# OLM_OS_v142.net
KiCad netlist of a schematic drawn in EAGLE
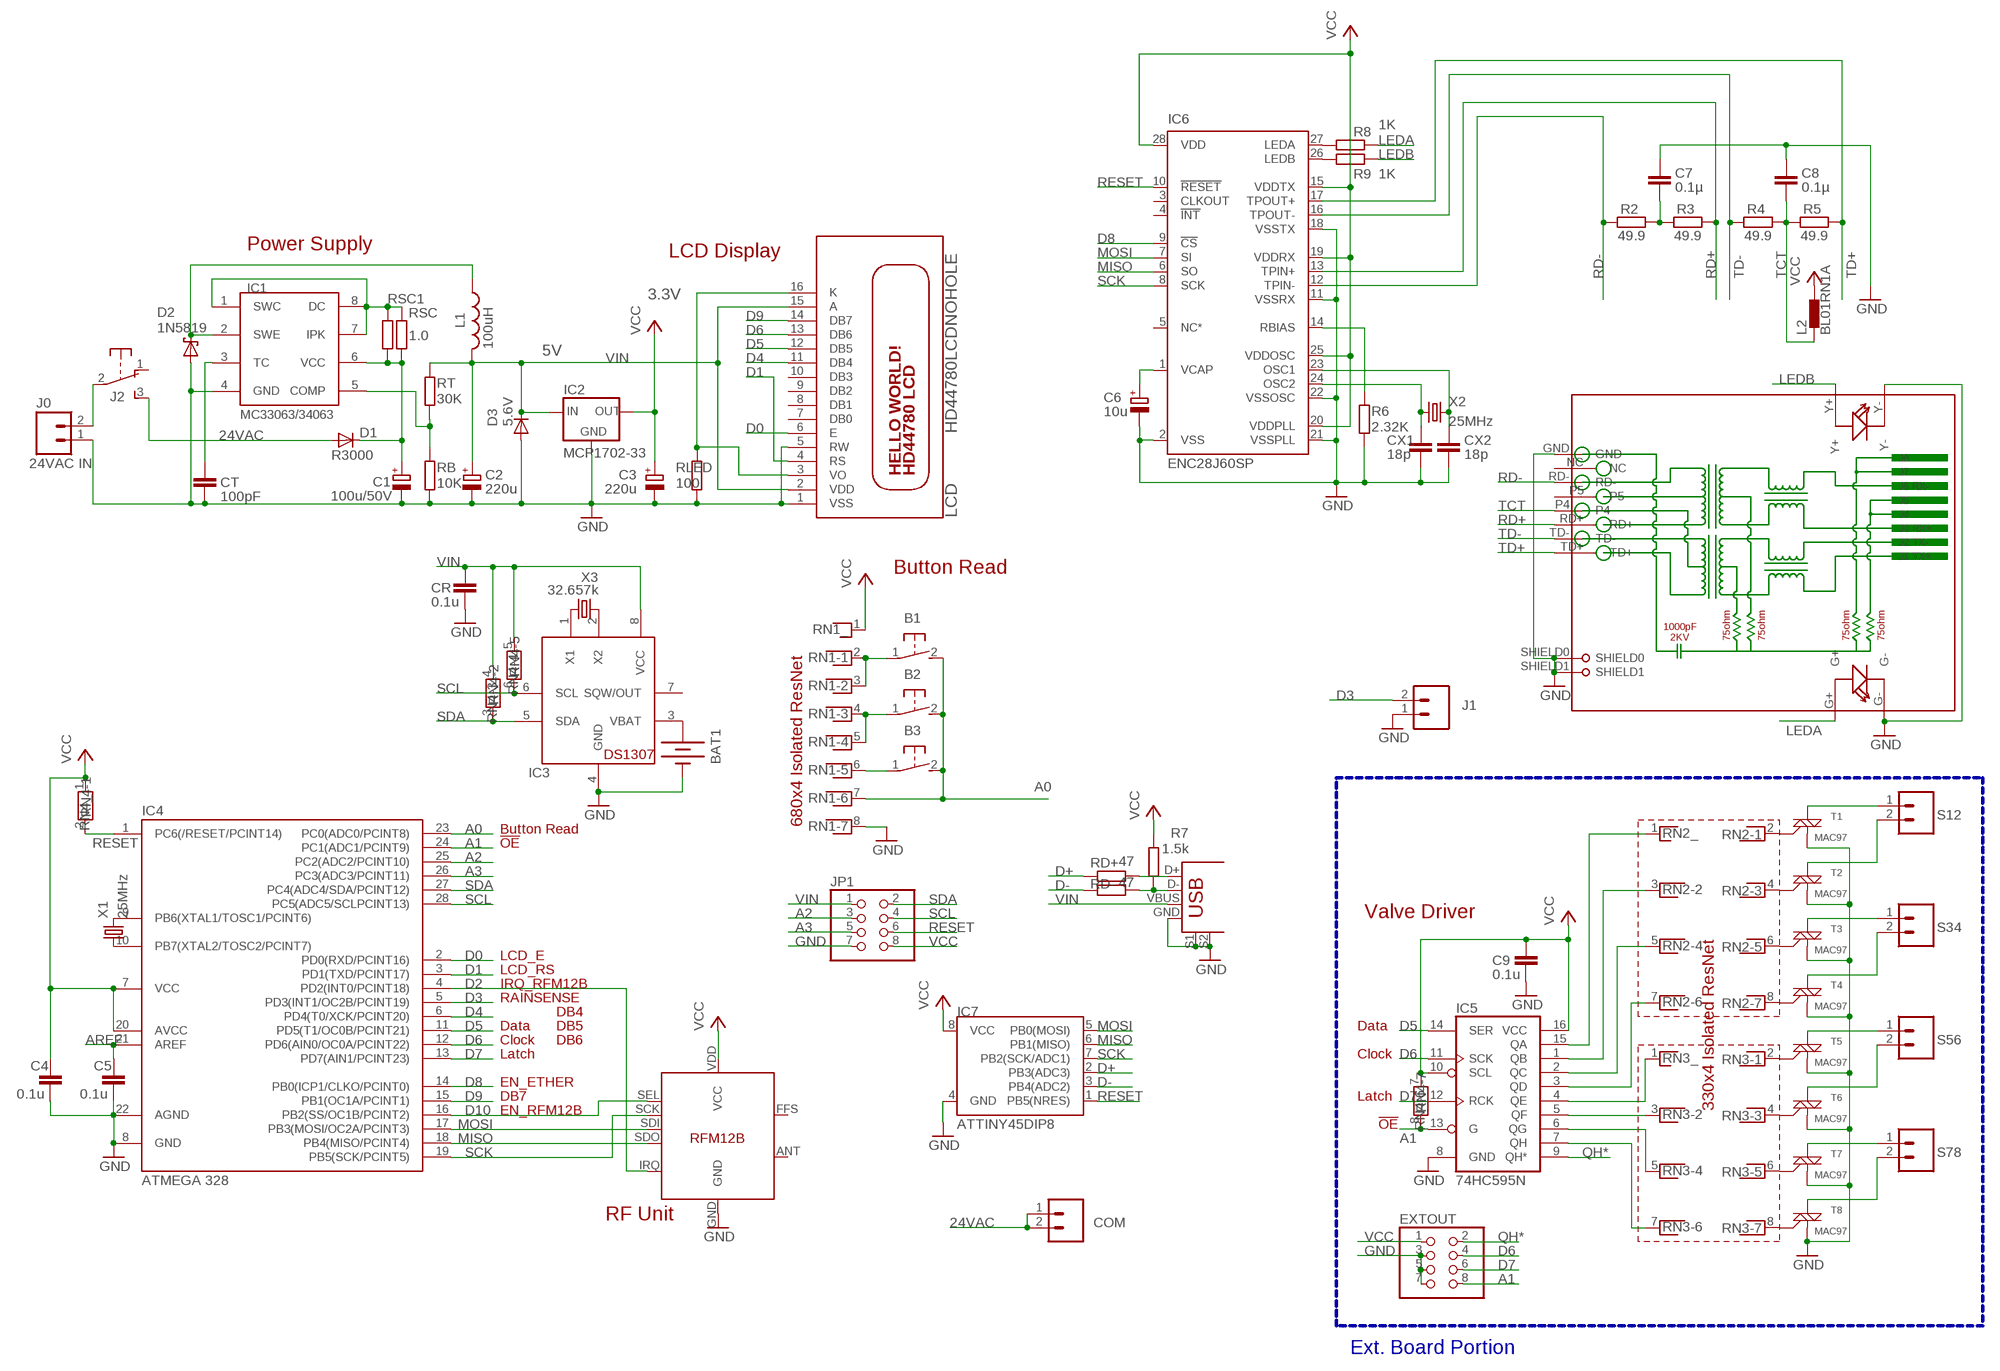
[diagram p0: schematic, sheet 1]

(export (version "E")
  (design (tool "Eeschema 10.0.6"))
  (components
    (comp (ref "B1")
      (value "31-XX")
      (footprint "eagle-import:B3F-31XX")
      (libsource (lib "eagle-import") (part "31-XX"))
    )
    (comp (ref "B2")
      (value "31-XX")
      (footprint "eagle-import:B3F-31XX")
      (libsource (lib "eagle-import") (part "31-XX"))
    )
    (comp (ref "B3")
      (value "31-XX")
      (footprint "eagle-import:B3F-31XX")
      (libsource (lib "eagle-import") (part "31-XX"))
    )
    (comp (ref "BAT1")
      (value "BATTERY12PTH")
      (footprint "eagle-import:BATTCON_12MM_PTH")
      (libsource (lib "eagle-import") (part "BATTERY12PTH"))
    )
    (comp (ref "C1")
      (value "100u/50V")
      (footprint "eagle-import:E3,5-8")
      (libsource (lib "eagle-import") (part "CPOL-EUE3.5-8"))
    )
    (comp (ref "C2")
      (value "220u")
      (footprint "eagle-import:E2-5")
      (libsource (lib "eagle-import") (part "CPOL-EUE2-5"))
    )
    (comp (ref "C3")
      (value "220u")
      (footprint "eagle-import:E2-5")
      (libsource (lib "eagle-import") (part "CPOL-EUE2-5"))
    )
    (comp (ref "C4")
      (value "0.1u")
      (footprint "eagle-import:C025-024X044")
      (libsource (lib "eagle-import") (part "C-EU025-024X044"))
    )
    (comp (ref "C5")
      (value "0.1u")
      (footprint "eagle-import:C025-024X044")
      (libsource (lib "eagle-import") (part "C-EU025-024X044"))
    )
    (comp (ref "C6")
      (value "10u")
      (footprint "eagle-import:E1,8-4")
      (libsource (lib "eagle-import") (part "CPOL-EUE1.8-4"))
    )
    (comp (ref "C7")
      (value "0.1µ")
      (footprint "eagle-import:C025-024X044")
      (libsource (lib "eagle-import") (part "resistor_C-EU025-024X044"))
    )
    (comp (ref "C8")
      (value "0.1µ")
      (footprint "eagle-import:C025-024X044")
      (libsource (lib "eagle-import") (part "resistor_C-EU025-024X044"))
    )
    (comp (ref "C9")
      (value "0.1u")
      (footprint "eagle-import:C025-024X044")
      (libsource (lib "eagle-import") (part "C-EU025-024X044"))
    )
    (comp (ref "COM")
      (value "M025MM")
      (footprint "eagle-import:SCREWTERMINAL-5MM-2")
      (libsource (lib "eagle-import") (part "M025MM"))
    )
    (comp (ref "CR")
      (value "0.1u")
      (footprint "eagle-import:C025-024X044")
      (libsource (lib "eagle-import") (part "C-EU025-024X044"))
    )
    (comp (ref "CT")
      (value "100pF")
      (footprint "eagle-import:C025-024X044")
      (libsource (lib "eagle-import") (part "C-EU025-024X044"))
    )
    (comp (ref "CX1")
      (value "18p")
      (footprint "eagle-import:C025-024X044")
      (libsource (lib "eagle-import") (part "resistor_C-EU025-024X044"))
    )
    (comp (ref "CX2")
      (value "18p")
      (footprint "eagle-import:C025-024X044")
      (libsource (lib "eagle-import") (part "resistor_C-EU025-024X044"))
    )
    (comp (ref "D1")
      (value "R3000")
      (footprint "eagle-import:DO41-7.6")
      (libsource (lib "eagle-import") (part "DIODE-DO41-7.6"))
    )
    (comp (ref "D2")
      (value "1N5819")
      (footprint "eagle-import:DO41-7.6")
      (libsource (lib "eagle-import") (part "1N5817-B"))
    )
    (comp (ref "D3")
      (value "5.6V")
      (footprint "eagle-import:DO35-7")
      (libsource (lib "eagle-import") (part "1N4148DO35-7"))
    )
    (comp (ref "EXTOUT")
      (value "PINHD-2X4")
      (footprint "eagle-import:2X04")
      (libsource (lib "eagle-import") (part "PINHD-2X4"))
    )
    (comp (ref "IC1")
      (value "MC33063/MC34063P")
      (footprint "eagle-import:DIL08")
      (libsource (lib "eagle-import") (part "MC33063/MC34063P"))
    )
    (comp (ref "IC2")
      (value "MCP1702-33")
      (footprint "eagle-import:TO92-INLINE")
      (libsource (lib "eagle-import") (part "MCP1700INLINE"))
    )
    (comp (ref "IC3")
      (value "DS1307")
      (footprint "eagle-import:DIL08")
      (libsource (lib "eagle-import") (part "DS1307"))
    )
    (comp (ref "IC4")
      (value "ATMEGA 328")
      (footprint "eagle-import:DIL28-3")
      (libsource (lib "eagle-import") (part "ATMEGA48/88/168-PU"))
    )
    (comp (ref "IC5")
      (value "74HC595N")
      (footprint "eagle-import:DIL16")
      (libsource (lib "eagle-import") (part "74595NLS"))
    )
    (comp (ref "IC6")
      (value "ENC28J60SP")
      (footprint "eagle-import:DIL28-3")
      (fields (field (name "MF") "MICROCHIP") (field (name "MPN") "ENC28J60/SP"))
      (libsource (lib "eagle-import") (part "ENC28J60SP"))
    )
    (comp (ref "IC7")
      (value "ATTINY45DIP8")
      (footprint "eagle-import:DIP08")
      (libsource (lib "eagle-import") (part "ATTINY45DIP8"))
    )
    (comp (ref "IC8")
      (value "RFM12B")
      (footprint "eagle-import:RFM12B")
      (libsource (lib "eagle-import") (part "RFM12B"))
    )
    (comp (ref "J0")
      (value "24VAC IN")
      (footprint "eagle-import:SCREWTERMINAL-5MM-2")
      (libsource (lib "eagle-import") (part "M025MM"))
    )
    (comp (ref "J1")
      (value "M025MM")
      (footprint "eagle-import:SCREWTERMINAL-5MM-2")
      (libsource (lib "eagle-import") (part "M025MM"))
    )
    (comp (ref "J2")
      (value "EG1206")
      (footprint "eagle-import:EG1206")
      (libsource (lib "eagle-import") (part "EG1206"))
    )
    (comp (ref "JP1")
      (value "PINHD-2X4")
      (footprint "eagle-import:2X04")
      (libsource (lib "eagle-import") (part "PINHD-2X4"))
    )
    (comp (ref "L1")
      (value "100uH")
      (footprint "eagle-import:6000-XXXX-RC")
      (libsource (lib "eagle-import") (part "L-US6000-XXX-RC"))
    )
    (comp (ref "L2")
      (value "BL01RN1A")
      (footprint "eagle-import:BL01RN1A")
      (libsource (lib "eagle-import") (part "BL01RN1A"))
    )
    (comp (ref "LCD")
      (value "HD44780LCDNOHOLE")
      (footprint "eagle-import:LCD1602A")
      (libsource (lib "eagle-import") (part "HD44780LCDNOHOLE"))
    )
    (comp (ref "R2")
      (value "49.9")
      (footprint "eagle-import:0204_7")
      (libsource (lib "eagle-import") (part "R-EU_0204/7"))
    )
    (comp (ref "R3")
      (value "49.9")
      (footprint "eagle-import:0204_7")
      (libsource (lib "eagle-import") (part "R-EU_0204/7"))
    )
    (comp (ref "R4")
      (value "49.9")
      (footprint "eagle-import:0204_7")
      (libsource (lib "eagle-import") (part "R-EU_0204/7"))
    )
    (comp (ref "R5")
      (value "49.9")
      (footprint "eagle-import:0204_7")
      (libsource (lib "eagle-import") (part "R-EU_0204/7"))
    )
    (comp (ref "R6")
      (value "2.32K")
      (footprint "eagle-import:0204_7")
      (libsource (lib "eagle-import") (part "R-EU_0204/7"))
    )
    (comp (ref "R7")
      (value "1.5k")
      (footprint "eagle-import:0204_7")
      (libsource (lib "eagle-import") (part "R-EU_0204/7"))
    )
    (comp (ref "R8")
      (value "1K")
      (footprint "eagle-import:0204_7")
      (libsource (lib "eagle-import") (part "R-EU_0204/7"))
    )
    (comp (ref "R9")
      (value "1K")
      (footprint "eagle-import:0204_7")
      (libsource (lib "eagle-import") (part "R-EU_0204/7"))
    )
    (comp (ref "RB")
      (value "10K")
      (footprint "eagle-import:0204_7")
      (libsource (lib "eagle-import") (part "R-EU_0204/7"))
    )
    (comp (ref "RD+")
      (value "47")
      (footprint "eagle-import:0204_7")
      (libsource (lib "eagle-import") (part "R-EU_0204/7"))
    )
    (comp (ref "RD-")
      (value "47")
      (footprint "eagle-import:0204_7")
      (libsource (lib "eagle-import") (part "R-EU_0204/7"))
    )
    (comp (ref "RJ1")
      (value "HR911105A")
      (footprint "eagle-import:HR911105A")
      (libsource (lib "eagle-import") (part "HR911105A"))
    )
    (comp (ref "RLED")
      (value "100")
      (footprint "eagle-import:0204_7")
      (libsource (lib "eagle-import") (part "R-EU_0204/7"))
    )
    (comp (ref "RN1")
      (value "RNX7")
      (footprint "eagle-import:RN-8")
      (libsource (lib "eagle-import") (part "RNX7"))
    )
    (comp (ref "RN2")
      (value "RNX7")
      (footprint "eagle-import:RN-8")
      (libsource (lib "eagle-import") (part "RNX7"))
    )
    (comp (ref "RN3")
      (value "RNX7")
      (footprint "eagle-import:RN-8")
      (libsource (lib "eagle-import") (part "RNX7"))
    )
    (comp (ref "RN4")
      (value "RNX7")
      (footprint "eagle-import:RN-8")
      (libsource (lib "eagle-import") (part "RNX7"))
    )
    (comp (ref "RSC")
      (value "1.0")
      (footprint "eagle-import:0204_7")
      (libsource (lib "eagle-import") (part "R-EU_0204/7"))
    )
    (comp (ref "RSC1")
      (value "1.0")
      (footprint "eagle-import:0204_7")
      (libsource (lib "eagle-import") (part "R-EU_0204/7"))
    )
    (comp (ref "RT")
      (value "30K")
      (footprint "eagle-import:0204_7")
      (libsource (lib "eagle-import") (part "R-EU_0204/7"))
    )
    (comp (ref "S12")
      (value "M025MM")
      (footprint "eagle-import:SCREWTERMINAL-5MM-2")
      (libsource (lib "eagle-import") (part "M025MM"))
    )
    (comp (ref "S34")
      (value "M025MM")
      (footprint "eagle-import:SCREWTERMINAL-5MM-2")
      (libsource (lib "eagle-import") (part "M025MM"))
    )
    (comp (ref "S56")
      (value "M025MM")
      (footprint "eagle-import:SCREWTERMINAL-5MM-2")
      (libsource (lib "eagle-import") (part "M025MM"))
    )
    (comp (ref "S78")
      (value "M025MM")
      (footprint "eagle-import:SCREWTERMINAL-5MM-2")
      (libsource (lib "eagle-import") (part "M025MM"))
    )
    (comp (ref "T1")
      (value "MAC97")
      (footprint "eagle-import:TO-92")
      (libsource (lib "eagle-import") (part "LX807DE"))
    )
    (comp (ref "T2")
      (value "MAC97")
      (footprint "eagle-import:TO-92")
      (libsource (lib "eagle-import") (part "LX807DE"))
    )
    (comp (ref "T3")
      (value "MAC97")
      (footprint "eagle-import:TO-92")
      (libsource (lib "eagle-import") (part "LX807DE"))
    )
    (comp (ref "T4")
      (value "MAC97")
      (footprint "eagle-import:TO-92")
      (libsource (lib "eagle-import") (part "LX807DE"))
    )
    (comp (ref "T5")
      (value "MAC97")
      (footprint "eagle-import:TO-92")
      (libsource (lib "eagle-import") (part "LX807DE"))
    )
    (comp (ref "T6")
      (value "MAC97")
      (footprint "eagle-import:TO-92")
      (libsource (lib "eagle-import") (part "LX807DE"))
    )
    (comp (ref "T7")
      (value "MAC97")
      (footprint "eagle-import:TO-92")
      (libsource (lib "eagle-import") (part "LX807DE"))
    )
    (comp (ref "T8")
      (value "MAC97")
      (footprint "eagle-import:TO-92")
      (libsource (lib "eagle-import") (part "LX807DE"))
    )
    (comp (ref "USB")
      (value "USB+SHIELD")
      (footprint "eagle-import:USB-B-PTH")
      (libsource (lib "eagle-import") (part "USB+SHIELD"))
    )
    (comp (ref "X1")
      (value "25MHz")
      (footprint "eagle-import:HC49US")
      (libsource (lib "eagle-import") (part "CRYSTALHC49US"))
    )
    (comp (ref "X2")
      (value "25MHz")
      (footprint "eagle-import:HC49US")
      (libsource (lib "eagle-import") (part "CRYSTALHC49US"))
    )
    (comp (ref "X3")
      (value "32.657k")
      (footprint "eagle-import:TC26H")
      (libsource (lib "eagle-import") (part "crystal_CRYSTALTC26H"))
    )
  )
  (nets
    (net (code "1") (name "/24VAC") (class "Default")
      (node (ref "COM") (pin "1") (pinfunction "1_1") (pintype "passive"))
      (node (ref "COM") (pin "2") (pinfunction "2_2") (pintype "passive"))
      (node (ref "D1") (pin "A") (pinfunction "A_A") (pintype "passive"))
      (node (ref "J2") (pin "3") (pinfunction "S_3") (pintype "passive"))
    )
    (net (code "2") (name "/A0") (class "Default")
      (node (ref "B1") (pin "2") (pinfunction "S_2") (pintype "passive"))
      (node (ref "B2") (pin "2") (pinfunction "S_2") (pintype "passive"))
      (node (ref "B3") (pin "2") (pinfunction "S_2") (pintype "passive"))
      (node (ref "IC4") (pin "23") (pinfunction "PC0(ADC0/PCINT8)_23") (pintype "bidirectional"))
      (node (ref "RN1") (pin "7") (pinfunction "1_7") (pintype "passive"))
    )
    (net (code "3") (name "/A1") (class "Default")
      (node (ref "EXTOUT") (pin "8") (pinfunction "8_8") (pintype "passive"))
      (node (ref "IC4") (pin "24") (pinfunction "PC1(ADC1/PCINT9)_24") (pintype "bidirectional"))
      (node (ref "IC5") (pin "13") (pinfunction "G_13") (pintype "input"))
      (node (ref "RN4") (pin "8") (pinfunction "1_8") (pintype "passive"))
    )
    (net (code "4") (name "/A2") (class "Default")
      (node (ref "IC4") (pin "25") (pinfunction "PC2(ADC2/PCINT10)_25") (pintype "bidirectional"))
      (node (ref "JP1") (pin "3") (pinfunction "3_3") (pintype "passive"))
    )
    (net (code "5") (name "/A3") (class "Default")
      (node (ref "IC4") (pin "26") (pinfunction "PC3(ADC3/PCINT11)_26") (pintype "bidirectional"))
      (node (ref "JP1") (pin "5") (pinfunction "5_5") (pintype "passive"))
    )
    (net (code "6") (name "/AREF") (class "Default")
      (node (ref "C5") (pin "1") (pinfunction "1_1") (pintype "passive"))
      (node (ref "IC4") (pin "21") (pinfunction "AREF_21") (pintype "passive"))
    )
    (net (code "7") (name "/D+") (class "Default")
      (node (ref "IC7") (pin "2") (pinfunction "PB3(ADC3)_2") (pintype "bidirectional"))
      (node (ref "RD+") (pin "1") (pinfunction "1_1") (pintype "passive"))
    )
    (net (code "8") (name "/D-") (class "Default")
      (node (ref "IC7") (pin "3") (pinfunction "PB4(ADC2)_3") (pintype "bidirectional"))
      (node (ref "RD-") (pin "1") (pinfunction "1_1") (pintype "passive"))
    )
    (net (code "9") (name "/D0") (class "Default")
      (node (ref "IC4") (pin "2") (pinfunction "PD0(RXD/PCINT16)_2") (pintype "bidirectional"))
      (node (ref "LCD") (pin "6") (pinfunction "E_6") (pintype "input"))
    )
    (net (code "10") (name "/D1") (class "Default")
      (node (ref "IC4") (pin "3") (pinfunction "PD1(TXD/PCINT17)_3") (pintype "bidirectional"))
      (node (ref "LCD") (pin "4") (pinfunction "RS_4") (pintype "input"))
    )
    (net (code "11") (name "/D2") (class "Default")
      (node (ref "IC4") (pin "4") (pinfunction "PD2(INT0/PCINT18)_4") (pintype "bidirectional"))
      (node (ref "IC8") (pin "IRQ") (pinfunction "IRQ_IRQ") (pintype "open_collector"))
    )
    (net (code "12") (name "/D3") (class "Default")
      (node (ref "IC4") (pin "5") (pinfunction "PD3(INT1/OC2B/PCINT19)_5") (pintype "bidirectional"))
      (node (ref "J1") (pin "2") (pinfunction "2_2") (pintype "passive"))
    )
    (net (code "13") (name "/D4") (class "Default")
      (node (ref "IC4") (pin "6") (pinfunction "PD4(T0/XCK/PCINT20)_6") (pintype "bidirectional"))
      (node (ref "LCD") (pin "11") (pinfunction "DB4_11") (pintype "bidirectional"))
    )
    (net (code "14") (name "/D5") (class "Default")
      (node (ref "IC4") (pin "11") (pinfunction "PD5(T1/OC0B/PCINT21)_11") (pintype "bidirectional"))
      (node (ref "IC5") (pin "14") (pinfunction "SER_14") (pintype "input"))
      (node (ref "LCD") (pin "12") (pinfunction "DB5_12") (pintype "bidirectional"))
    )
    (net (code "15") (name "/D6") (class "Default")
      (node (ref "EXTOUT") (pin "4") (pinfunction "4_4") (pintype "passive"))
      (node (ref "IC4") (pin "12") (pinfunction "PD6(AIN0/OC0A/PCINT22)_12") (pintype "bidirectional"))
      (node (ref "IC5") (pin "11") (pinfunction "SCK_11") (pintype "input"))
      (node (ref "LCD") (pin "13") (pinfunction "DB6_13") (pintype "bidirectional"))
    )
    (net (code "16") (name "/D7") (class "Default")
      (node (ref "EXTOUT") (pin "6") (pinfunction "6_6") (pintype "passive"))
      (node (ref "IC4") (pin "13") (pinfunction "PD7(AIN1/PCINT23)_13") (pintype "bidirectional"))
      (node (ref "IC5") (pin "12") (pinfunction "RCK_12") (pintype "input"))
    )
    (net (code "17") (name "/D8") (class "Default")
      (node (ref "IC4") (pin "14") (pinfunction "PB0(ICP1/CLKO/PCINT0)_14") (pintype "bidirectional"))
      (node (ref "IC6") (pin "9") (pinfunction "~{CS}_9") (pintype "input"))
    )
    (net (code "18") (name "/D9") (class "Default")
      (node (ref "IC4") (pin "15") (pinfunction "PB1(OC1A/PCINT1)_15") (pintype "bidirectional"))
      (node (ref "LCD") (pin "14") (pinfunction "DB7_14") (pintype "bidirectional"))
    )
    (net (code "19") (name "/D10") (class "Default")
      (node (ref "IC4") (pin "16") (pinfunction "PB2(SS/OC1B/PCINT2)_16") (pintype "bidirectional"))
      (node (ref "IC8") (pin "SEL") (pinfunction "SEL_SEL") (pintype "input"))
    )
    (net (code "20") (name "/LEDA") (class "Default")
      (node (ref "R8") (pin "2") (pinfunction "2_2") (pintype "passive"))
      (node (ref "RJ1") (pin "G+") (pinfunction "G+_G+") (pintype "bidirectional"))
    )
    (net (code "21") (name "/LEDB") (class "Default")
      (node (ref "R9") (pin "2") (pinfunction "2_2") (pintype "passive"))
      (node (ref "RJ1") (pin "Y+") (pinfunction "Y+_Y+") (pintype "bidirectional"))
    )
    (net (code "22") (name "/MISO") (class "Default")
      (node (ref "IC4") (pin "18") (pinfunction "PB4(MISO/PCINT4)_18") (pintype "bidirectional"))
      (node (ref "IC6") (pin "6") (pinfunction "SO_6") (pintype "output"))
      (node (ref "IC7") (pin "6") (pinfunction "PB1(MISO)_6") (pintype "bidirectional"))
      (node (ref "IC8") (pin "SDO") (pinfunction "SDO_SDO") (pintype "output"))
    )
    (net (code "23") (name "/MOSI") (class "Default")
      (node (ref "IC4") (pin "17") (pinfunction "PB3(MOSI/OC2A/PCINT3)_17") (pintype "bidirectional"))
      (node (ref "IC6") (pin "7") (pinfunction "SI_7") (pintype "input"))
      (node (ref "IC7") (pin "5") (pinfunction "PB0(MOSI)_5") (pintype "bidirectional"))
      (node (ref "IC8") (pin "SDI") (pinfunction "SDI_SDI") (pintype "input"))
    )
    (net (code "24") (name "/QH*") (class "Default")
      (node (ref "EXTOUT") (pin "2") (pinfunction "2_2") (pintype "passive"))
      (node (ref "IC5") (pin "9") (pinfunction "QH*_9") (pintype "tri_state"))
    )
    (net (code "25") (name "/RD+") (class "Default")
      (node (ref "IC6") (pin "13") (pinfunction "TPIN+_13") (pintype "input"))
      (node (ref "R3") (pin "2") (pinfunction "2_2") (pintype "passive"))
      (node (ref "RJ1") (pin "RD+") (pinfunction "RD+_RD+") (pintype "bidirectional"))
    )
    (net (code "26") (name "/RD-") (class "Default")
      (node (ref "IC6") (pin "12") (pinfunction "TPIN-_12") (pintype "input"))
      (node (ref "R2") (pin "1") (pinfunction "1_1") (pintype "passive"))
      (node (ref "RJ1") (pin "RD-") (pinfunction "RD-_RD-") (pintype "bidirectional"))
    )
    (net (code "27") (name "/RESET") (class "Default")
      (node (ref "IC4") (pin "1") (pinfunction "PC6(/RESET/PCINT14)_1") (pintype "bidirectional"))
      (node (ref "IC6") (pin "10") (pinfunction "~{RESET}_10") (pintype "input"))
      (node (ref "IC7") (pin "1") (pinfunction "PB5(NRES)_1") (pintype "bidirectional"))
      (node (ref "JP1") (pin "6") (pinfunction "6_6") (pintype "passive"))
      (node (ref "RN4") (pin "2") (pinfunction "1_2") (pintype "passive"))
    )
    (net (code "28") (name "/SCK") (class "Default")
      (node (ref "IC4") (pin "19") (pinfunction "PB5(SCK/PCINT5)_19") (pintype "bidirectional"))
      (node (ref "IC6") (pin "8") (pinfunction "SCK_8") (pintype "input"))
      (node (ref "IC7") (pin "7") (pinfunction "PB2(SCK/ADC1)_7") (pintype "bidirectional"))
      (node (ref "IC8") (pin "SCK") (pinfunction "SCK_SCK") (pintype "input"))
    )
    (net (code "29") (name "/SCL") (class "Default")
      (node (ref "IC3") (pin "6") (pinfunction "SCL_6") (pintype "bidirectional"))
      (node (ref "IC4") (pin "28") (pinfunction "PC5(ADC5/SCLPCINT13)_28") (pintype "bidirectional"))
      (node (ref "JP1") (pin "4") (pinfunction "4_4") (pintype "passive"))
      (node (ref "RN4") (pin "6") (pinfunction "1_6") (pintype "passive"))
    )
    (net (code "30") (name "/SDA") (class "Default")
      (node (ref "IC3") (pin "5") (pinfunction "SDA_5") (pintype "bidirectional"))
      (node (ref "IC4") (pin "27") (pinfunction "PC4(ADC4/SDA/PCINT12)_27") (pintype "bidirectional"))
      (node (ref "JP1") (pin "2") (pinfunction "2_2") (pintype "passive"))
      (node (ref "RN4") (pin "3") (pinfunction "1_3") (pintype "passive"))
    )
    (net (code "31") (name "/TCT") (class "Default")
      (node (ref "C8") (pin "2") (pinfunction "2_2") (pintype "passive"))
      (node (ref "L2") (pin "1") (pinfunction "1_1") (pintype "passive"))
      (node (ref "R4") (pin "2") (pinfunction "2_2") (pintype "passive"))
      (node (ref "R5") (pin "1") (pinfunction "1_1") (pintype "passive"))
      (node (ref "RJ1") (pin "P4") (pinfunction "P4_P4") (pintype "bidirectional"))
    )
    (net (code "32") (name "/TD+") (class "Default")
      (node (ref "IC6") (pin "17") (pinfunction "TPOUT+_17") (pintype "output"))
      (node (ref "R5") (pin "2") (pinfunction "2_2") (pintype "passive"))
      (node (ref "RJ1") (pin "TD+") (pinfunction "TD+_TD+") (pintype "bidirectional"))
    )
    (net (code "33") (name "/TD-") (class "Default")
      (node (ref "IC6") (pin "16") (pinfunction "TPOUT-_16") (pintype "output"))
      (node (ref "R4") (pin "1") (pinfunction "1_1") (pintype "passive"))
      (node (ref "RJ1") (pin "TD-") (pinfunction "TD-_TD-") (pintype "bidirectional"))
    )
    (net (code "34") (name "/VIN") (class "Default")
      (node (ref "C2") (pin "+") (pinfunction "+_+") (pintype "passive"))
      (node (ref "CR") (pin "1") (pinfunction "1_1") (pintype "passive"))
      (node (ref "D3") (pin "C") (pinfunction "C_C") (pintype "passive"))
      (node (ref "IC2") (pin "2") (pinfunction "IN_2") (pintype "input"))
      (node (ref "IC3") (pin "8") (pinfunction "VCC_8") (pintype "power_in"))
      (node (ref "JP1") (pin "1") (pinfunction "1_1") (pintype "passive"))
      (node (ref "L1") (pin "2") (pinfunction "2_2") (pintype "passive"))
      (node (ref "LCD") (pin "15") (pinfunction "A_15") (pintype "input"))
      (node (ref "LCD") (pin "2") (pinfunction "VDD_2") (pintype "power_in"))
      (node (ref "RN4") (pin "4") (pinfunction "1_4") (pintype "passive"))
      (node (ref "RN4") (pin "5") (pinfunction "1_5") (pintype "passive"))
      (node (ref "RT") (pin "1") (pinfunction "1_1") (pintype "passive"))
      (node (ref "USB") (pin "VBUS") (pinfunction "VBUS_VBUS") (pintype "bidirectional"))
    )
    (net (code "35") (name "GND") (class "Default")
      (node (ref "BAT1") (pin "GND") (pinfunction "-_GND") (pintype "power_in"))
      (node (ref "C1") (pin "-") (pinfunction "-_-") (pintype "passive"))
      (node (ref "C2") (pin "-") (pinfunction "-_-") (pintype "passive"))
      (node (ref "C3") (pin "-") (pinfunction "-_-") (pintype "passive"))
      (node (ref "C4") (pin "2") (pinfunction "2_2") (pintype "passive"))
      (node (ref "C5") (pin "2") (pinfunction "2_2") (pintype "passive"))
      (node (ref "C6") (pin "-") (pinfunction "-_-") (pintype "passive"))
      (node (ref "C7") (pin "1") (pinfunction "1_1") (pintype "passive"))
      (node (ref "C8") (pin "1") (pinfunction "1_1") (pintype "passive"))
      (node (ref "C9") (pin "2") (pinfunction "2_2") (pintype "passive"))
      (node (ref "CR") (pin "2") (pinfunction "2_2") (pintype "passive"))
      (node (ref "CT") (pin "2") (pinfunction "2_2") (pintype "passive"))
      (node (ref "CX1") (pin "2") (pinfunction "2_2") (pintype "passive"))
      (node (ref "CX2") (pin "2") (pinfunction "2_2") (pintype "passive"))
      (node (ref "D2") (pin "A") (pinfunction "A_A") (pintype "passive"))
      (node (ref "D3") (pin "A") (pinfunction "A_A") (pintype "passive"))
      (node (ref "EXTOUT") (pin "3") (pinfunction "3_3") (pintype "passive"))
      (node (ref "EXTOUT") (pin "5") (pinfunction "5_5") (pintype "passive"))
      (node (ref "EXTOUT") (pin "7") (pinfunction "7_7") (pintype "passive"))
      (node (ref "IC1") (pin "4") (pinfunction "GND_4") (pintype "power_in"))
      (node (ref "IC2") (pin "1") (pinfunction "GND_1") (pintype "input"))
      (node (ref "IC3") (pin "4") (pinfunction "GND_4") (pintype "power_in"))
      (node (ref "IC4") (pin "22") (pinfunction "AGND_22") (pintype "power_in"))
      (node (ref "IC4") (pin "8") (pinfunction "GND_8") (pintype "power_in"))
      (node (ref "IC5") (pin "8") (pinfunction "GND_8") (pintype "power_in"))
      (node (ref "IC6") (pin "11") (pinfunction "VSSRX_11") (pintype "input"))
      (node (ref "IC6") (pin "18") (pinfunction "VSSTX_18") (pintype "input"))
      (node (ref "IC6") (pin "2") (pinfunction "VSS_2") (pintype "input"))
      (node (ref "IC6") (pin "21") (pinfunction "VSSPLL_21") (pintype "input"))
      (node (ref "IC6") (pin "22") (pinfunction "VSSOSC_22") (pintype "input"))
      (node (ref "IC7") (pin "4") (pinfunction "GND_4") (pintype "bidirectional"))
      (node (ref "IC8") (pin "GND") (pinfunction "GND_GND") (pintype "power_in"))
      (node (ref "J0") (pin "1") (pinfunction "1_1") (pintype "passive"))
      (node (ref "J1") (pin "1") (pinfunction "1_1") (pintype "passive"))
      (node (ref "JP1") (pin "7") (pinfunction "7_7") (pintype "passive"))
      (node (ref "LCD") (pin "1") (pinfunction "VSS_1") (pintype "power_in"))
      (node (ref "LCD") (pin "5") (pinfunction "RW_5") (pintype "input"))
      (node (ref "R6") (pin "2") (pinfunction "2_2") (pintype "passive"))
      (node (ref "RB") (pin "2") (pinfunction "2_2") (pintype "passive"))
      (node (ref "RJ1") (pin "G-") (pinfunction "G-_G-") (pintype "bidirectional"))
      (node (ref "RJ1") (pin "GND") (pinfunction "GND_GND") (pintype "bidirectional"))
      (node (ref "RJ1") (pin "SHIELD0") (pinfunction "SHIELD0_SHIELD0") (pintype "bidirectional"))
      (node (ref "RJ1") (pin "SHIELD1") (pinfunction "SHIELD1_SHIELD1") (pintype "bidirectional"))
      (node (ref "RJ1") (pin "Y-") (pinfunction "Y-_Y-") (pintype "bidirectional"))
      (node (ref "RLED") (pin "2") (pinfunction "2_2") (pintype "passive"))
      (node (ref "RN1") (pin "8") (pinfunction "1_8") (pintype "passive"))
      (node (ref "T1") (pin "1") (pinfunction "M1_1") (pintype "bidirectional"))
      (node (ref "T2") (pin "1") (pinfunction "M1_1") (pintype "bidirectional"))
      (node (ref "T3") (pin "1") (pinfunction "M1_1") (pintype "bidirectional"))
      (node (ref "T4") (pin "1") (pinfunction "M1_1") (pintype "bidirectional"))
      (node (ref "T5") (pin "1") (pinfunction "M1_1") (pintype "bidirectional"))
      (node (ref "T6") (pin "1") (pinfunction "M1_1") (pintype "bidirectional"))
      (node (ref "T7") (pin "1") (pinfunction "M1_1") (pintype "bidirectional"))
      (node (ref "T8") (pin "1") (pinfunction "M1_1") (pintype "bidirectional"))
      (node (ref "USB") (pin "GND") (pinfunction "GND_GND") (pintype "bidirectional"))
      (node (ref "USB") (pin "S1") (pinfunction "P$1_S1") (pintype "bidirectional"))
      (node (ref "USB") (pin "S2") (pinfunction "P$2_S2") (pintype "bidirectional"))
    )
    (net (code "36") (name "Net-(B1-P)") (class "Default")
      (node (ref "B1") (pin "1") (pinfunction "P_1") (pintype "passive"))
      (node (ref "RN1") (pin "2") (pinfunction "1_2") (pintype "passive"))
      (node (ref "RN1") (pin "3") (pinfunction "1_3") (pintype "passive"))
    )
    (net (code "37") (name "Net-(B2-P)") (class "Default")
      (node (ref "B2") (pin "1") (pinfunction "P_1") (pintype "passive"))
      (node (ref "RN1") (pin "4") (pinfunction "1_4") (pintype "passive"))
      (node (ref "RN1") (pin "5") (pinfunction "1_5") (pintype "passive"))
    )
    (net (code "38") (name "Net-(B3-P)") (class "Default")
      (node (ref "B3") (pin "1") (pinfunction "P_1") (pintype "passive"))
      (node (ref "RN1") (pin "6") (pinfunction "1_6") (pintype "passive"))
    )
    (net (code "39") (name "Net-(BAT1-+)") (class "Default")
      (node (ref "BAT1") (pin "VCC@1") (pinfunction "+_VCC@1") (pintype "power_in"))
      (node (ref "IC3") (pin "3") (pinfunction "VBAT_3") (pintype "power_in"))
    )
    (net (code "40") (name "Net-(C7-Pad2)") (class "Default")
      (node (ref "C7") (pin "2") (pinfunction "2_2") (pintype "passive"))
      (node (ref "R2") (pin "2") (pinfunction "2_2") (pintype "passive"))
      (node (ref "R3") (pin "1") (pinfunction "1_1") (pintype "passive"))
    )
    (net (code "41") (name "Net-(IC1-COMP)") (class "Default")
      (node (ref "IC1") (pin "5") (pinfunction "COMP_5") (pintype "input"))
      (node (ref "RB") (pin "1") (pinfunction "1_1") (pintype "passive"))
      (node (ref "RT") (pin "2") (pinfunction "2_2") (pintype "passive"))
    )
    (net (code "42") (name "Net-(IC1-DC)") (class "Default")
      (node (ref "IC1") (pin "1") (pinfunction "SWC_1") (pintype "input"))
      (node (ref "IC1") (pin "7") (pinfunction "IPK_7") (pintype "bidirectional"))
      (node (ref "IC1") (pin "8") (pinfunction "DC_8") (pintype "input"))
      (node (ref "RSC") (pin "1") (pinfunction "1_1") (pintype "passive"))
      (node (ref "RSC1") (pin "1") (pinfunction "1_1") (pintype "passive"))
    )
    (net (code "43") (name "Net-(IC1-SWE)") (class "Default")
      (node (ref "D2") (pin "C") (pinfunction "C_C") (pintype "passive"))
      (node (ref "IC1") (pin "2") (pinfunction "SWE_2") (pintype "input"))
      (node (ref "L1") (pin "1") (pinfunction "1_1") (pintype "passive"))
    )
    (net (code "44") (name "Net-(IC1-TC)") (class "Default")
      (node (ref "CT") (pin "1") (pinfunction "1_1") (pintype "passive"))
      (node (ref "IC1") (pin "3") (pinfunction "TC_3") (pintype "input"))
    )
    (net (code "45") (name "Net-(IC1-VCC)") (class "Default")
      (node (ref "C1") (pin "+") (pinfunction "+_+") (pintype "passive"))
      (node (ref "D1") (pin "C") (pinfunction "C_C") (pintype "passive"))
      (node (ref "IC1") (pin "6") (pinfunction "VCC_6") (pintype "power_in"))
      (node (ref "RSC") (pin "2") (pinfunction "2_2") (pintype "passive"))
      (node (ref "RSC1") (pin "2") (pinfunction "2_2") (pintype "passive"))
    )
    (net (code "46") (name "Net-(IC3-X1)") (class "Default")
      (node (ref "IC3") (pin "1") (pinfunction "X1_1") (pintype "passive"))
      (node (ref "X3") (pin "1") (pinfunction "1_1") (pintype "passive"))
    )
    (net (code "47") (name "Net-(IC3-X2)") (class "Default")
      (node (ref "IC3") (pin "2") (pinfunction "X2_2") (pintype "passive"))
      (node (ref "X3") (pin "2") (pinfunction "2_2") (pintype "passive"))
    )
    (net (code "48") (name "Net-(IC4-PB6(XTAL1{slash}TOSC1{slash}PCINT6))") (class "Default")
      (node (ref "IC4") (pin "9") (pinfunction "PB6(XTAL1/TOSC1/PCINT6)_9") (pintype "bidirectional"))
      (node (ref "X1") (pin "2") (pinfunction "2_2") (pintype "passive"))
    )
    (net (code "49") (name "Net-(IC4-PB7(XTAL2{slash}TOSC2{slash}PCINT7))") (class "Default")
      (node (ref "IC4") (pin "10") (pinfunction "PB7(XTAL2/TOSC2/PCINT7)_10") (pintype "bidirectional"))
      (node (ref "X1") (pin "1") (pinfunction "1_1") (pintype "passive"))
    )
    (net (code "50") (name "Net-(IC5-QA)") (class "Default")
      (node (ref "IC5") (pin "15") (pinfunction "QA_15") (pintype "tri_state"))
      (node (ref "RN2") (pin "1") (pinfunction "1_1") (pintype "passive"))
    )
    (net (code "51") (name "Net-(IC5-QB)") (class "Default")
      (node (ref "IC5") (pin "1") (pinfunction "QB_1") (pintype "tri_state"))
      (node (ref "RN2") (pin "3") (pinfunction "1_3") (pintype "passive"))
    )
    (net (code "52") (name "Net-(IC5-QC)") (class "Default")
      (node (ref "IC5") (pin "2") (pinfunction "QC_2") (pintype "tri_state"))
      (node (ref "RN2") (pin "5") (pinfunction "1_5") (pintype "passive"))
    )
    (net (code "53") (name "Net-(IC5-QD)") (class "Default")
      (node (ref "IC5") (pin "3") (pinfunction "QD_3") (pintype "tri_state"))
      (node (ref "RN2") (pin "7") (pinfunction "1_7") (pintype "passive"))
    )
    (net (code "54") (name "Net-(IC5-QE)") (class "Default")
      (node (ref "IC5") (pin "4") (pinfunction "QE_4") (pintype "tri_state"))
      (node (ref "RN3") (pin "1") (pinfunction "1_1") (pintype "passive"))
    )
    (net (code "55") (name "Net-(IC5-QF)") (class "Default")
      (node (ref "IC5") (pin "5") (pinfunction "QF_5") (pintype "tri_state"))
      (node (ref "RN3") (pin "3") (pinfunction "1_3") (pintype "passive"))
    )
    (net (code "56") (name "Net-(IC5-QG)") (class "Default")
      (node (ref "IC5") (pin "6") (pinfunction "QG_6") (pintype "tri_state"))
      (node (ref "RN3") (pin "5") (pinfunction "1_5") (pintype "passive"))
    )
    (net (code "57") (name "Net-(IC5-QH)") (class "Default")
      (node (ref "IC5") (pin "7") (pinfunction "QH_7") (pintype "tri_state"))
      (node (ref "RN3") (pin "7") (pinfunction "1_7") (pintype "passive"))
    )
    (net (code "58") (name "Net-(IC6-LEDA)") (class "Default")
      (node (ref "IC6") (pin "27") (pinfunction "LEDA_27") (pintype "output"))
      (node (ref "R8") (pin "1") (pinfunction "1_1") (pintype "passive"))
    )
    (net (code "59") (name "Net-(IC6-LEDB)") (class "Default")
      (node (ref "IC6") (pin "26") (pinfunction "LEDB_26") (pintype "output"))
      (node (ref "R9") (pin "1") (pinfunction "1_1") (pintype "passive"))
    )
    (net (code "60") (name "Net-(IC6-OSC1)") (class "Default")
      (node (ref "CX2") (pin "1") (pinfunction "1_1") (pintype "passive"))
      (node (ref "IC6") (pin "23") (pinfunction "OSC1_23") (pintype "input"))
      (node (ref "X2") (pin "2") (pinfunction "2_2") (pintype "passive"))
    )
    (net (code "61") (name "Net-(IC6-OSC2)") (class "Default")
      (node (ref "CX1") (pin "1") (pinfunction "1_1") (pintype "passive"))
      (node (ref "IC6") (pin "24") (pinfunction "OSC2_24") (pintype "output"))
      (node (ref "X2") (pin "1") (pinfunction "1_1") (pintype "passive"))
    )
    (net (code "62") (name "Net-(IC6-RBIAS)") (class "Default")
      (node (ref "IC6") (pin "14") (pinfunction "RBIAS_14") (pintype "input"))
      (node (ref "R6") (pin "1") (pinfunction "1_1") (pintype "passive"))
    )
    (net (code "63") (name "Net-(IC6-VCAP)") (class "Default")
      (node (ref "C6") (pin "+") (pinfunction "+_+") (pintype "passive"))
      (node (ref "IC6") (pin "1") (pinfunction "VCAP_1") (pintype "input"))
    )
    (net (code "64") (name "Net-(J2-P)") (class "Default")
      (node (ref "J0") (pin "2") (pinfunction "2_2") (pintype "passive"))
      (node (ref "J2") (pin "2") (pinfunction "P_2") (pintype "passive"))
    )
    (net (code "65") (name "Net-(LCD-K)") (class "Default")
      (node (ref "LCD") (pin "16") (pinfunction "K_16") (pintype "input"))
      (node (ref "LCD") (pin "3") (pinfunction "VO_3") (pintype "input"))
      (node (ref "RLED") (pin "1") (pinfunction "1_1") (pintype "passive"))
    )
    (net (code "66") (name "Net-(R7-Pad1)") (class "Default")
      (node (ref "R7") (pin "1") (pinfunction "1_1") (pintype "passive"))
      (node (ref "RD-") (pin "2") (pinfunction "2_2") (pintype "passive"))
      (node (ref "USB") (pin "D-") (pinfunction "D-_D-") (pintype "bidirectional"))
    )
    (net (code "67") (name "Net-(RD+-Pad2)") (class "Default")
      (node (ref "RD+") (pin "2") (pinfunction "2_2") (pintype "passive"))
      (node (ref "USB") (pin "D+") (pinfunction "D+_D+") (pintype "bidirectional"))
    )
    (net (code "68") (name "Net-(RN2A-1)") (class "Default")
      (node (ref "RN2") (pin "2") (pinfunction "1_2") (pintype "passive"))
      (node (ref "T1") (pin "2") (pinfunction "G_2") (pintype "bidirectional"))
    )
    (net (code "69") (name "Net-(RN2C-1)") (class "Default")
      (node (ref "RN2") (pin "4") (pinfunction "1_4") (pintype "passive"))
      (node (ref "T2") (pin "2") (pinfunction "G_2") (pintype "bidirectional"))
    )
    (net (code "70") (name "Net-(RN2E-1)") (class "Default")
      (node (ref "RN2") (pin "6") (pinfunction "1_6") (pintype "passive"))
      (node (ref "T3") (pin "2") (pinfunction "G_2") (pintype "bidirectional"))
    )
    (net (code "71") (name "Net-(RN2G-1)") (class "Default")
      (node (ref "RN2") (pin "8") (pinfunction "1_8") (pintype "passive"))
      (node (ref "T4") (pin "2") (pinfunction "G_2") (pintype "bidirectional"))
    )
    (net (code "72") (name "Net-(RN3A-1)") (class "Default")
      (node (ref "RN3") (pin "2") (pinfunction "1_2") (pintype "passive"))
      (node (ref "T5") (pin "2") (pinfunction "G_2") (pintype "bidirectional"))
    )
    (net (code "73") (name "Net-(RN3C-1)") (class "Default")
      (node (ref "RN3") (pin "4") (pinfunction "1_4") (pintype "passive"))
      (node (ref "T6") (pin "2") (pinfunction "G_2") (pintype "bidirectional"))
    )
    (net (code "74") (name "Net-(RN3E-1)") (class "Default")
      (node (ref "RN3") (pin "6") (pinfunction "1_6") (pintype "passive"))
      (node (ref "T7") (pin "2") (pinfunction "G_2") (pintype "bidirectional"))
    )
    (net (code "75") (name "Net-(RN3G-1)") (class "Default")
      (node (ref "RN3") (pin "8") (pinfunction "1_8") (pintype "passive"))
      (node (ref "T8") (pin "2") (pinfunction "G_2") (pintype "bidirectional"))
    )
    (net (code "76") (name "Net-(T1-M2)") (class "Default")
      (node (ref "S12") (pin "1") (pinfunction "1_1") (pintype "passive"))
      (node (ref "T1") (pin "3") (pinfunction "M2_3") (pintype "bidirectional"))
    )
    (net (code "77") (name "Net-(T2-M2)") (class "Default")
      (node (ref "S12") (pin "2") (pinfunction "2_2") (pintype "passive"))
      (node (ref "T2") (pin "3") (pinfunction "M2_3") (pintype "bidirectional"))
    )
    (net (code "78") (name "Net-(T3-M2)") (class "Default")
      (node (ref "S34") (pin "1") (pinfunction "1_1") (pintype "passive"))
      (node (ref "T3") (pin "3") (pinfunction "M2_3") (pintype "bidirectional"))
    )
    (net (code "79") (name "Net-(T4-M2)") (class "Default")
      (node (ref "S34") (pin "2") (pinfunction "2_2") (pintype "passive"))
      (node (ref "T4") (pin "3") (pinfunction "M2_3") (pintype "bidirectional"))
    )
    (net (code "80") (name "Net-(T5-M2)") (class "Default")
      (node (ref "S56") (pin "1") (pinfunction "1_1") (pintype "passive"))
      (node (ref "T5") (pin "3") (pinfunction "M2_3") (pintype "bidirectional"))
    )
    (net (code "81") (name "Net-(T6-M2)") (class "Default")
      (node (ref "S56") (pin "2") (pinfunction "2_2") (pintype "passive"))
      (node (ref "T6") (pin "3") (pinfunction "M2_3") (pintype "bidirectional"))
    )
    (net (code "82") (name "Net-(T7-M2)") (class "Default")
      (node (ref "S78") (pin "1") (pinfunction "1_1") (pintype "passive"))
      (node (ref "T7") (pin "3") (pinfunction "M2_3") (pintype "bidirectional"))
    )
    (net (code "83") (name "Net-(T8-M2)") (class "Default")
      (node (ref "S78") (pin "2") (pinfunction "2_2") (pintype "passive"))
      (node (ref "T8") (pin "3") (pinfunction "M2_3") (pintype "bidirectional"))
    )
    (net (code "84") (name "VCC") (class "Default")
      (node (ref "C3") (pin "+") (pinfunction "+_+") (pintype "passive"))
      (node (ref "C4") (pin "1") (pinfunction "1_1") (pintype "passive"))
      (node (ref "C9") (pin "1") (pinfunction "1_1") (pintype "passive"))
      (node (ref "EXTOUT") (pin "1") (pinfunction "1_1") (pintype "passive"))
      (node (ref "IC2") (pin "3") (pinfunction "OUT_3") (pintype "passive"))
      (node (ref "IC4") (pin "20") (pinfunction "AVCC_20") (pintype "passive"))
      (node (ref "IC4") (pin "7") (pinfunction "VCC_7") (pintype "power_in"))
      (node (ref "IC5") (pin "10") (pinfunction "SCL_10") (pintype "input"))
      (node (ref "IC5") (pin "16") (pinfunction "VCC_16") (pintype "power_in"))
      (node (ref "IC6") (pin "15") (pinfunction "VDDTX_15") (pintype "input"))
      (node (ref "IC6") (pin "19") (pinfunction "VDDRX_19") (pintype "input"))
      (node (ref "IC6") (pin "20") (pinfunction "VDDPLL_20") (pintype "input"))
      (node (ref "IC6") (pin "25") (pinfunction "VDDOSC_25") (pintype "input"))
      (node (ref "IC6") (pin "28") (pinfunction "VDD_28") (pintype "input"))
      (node (ref "IC7") (pin "8") (pinfunction "VCC_8") (pintype "bidirectional"))
      (node (ref "IC8") (pin "VDD") (pinfunction "VCC_VDD") (pintype "power_in"))
      (node (ref "JP1") (pin "8") (pinfunction "8_8") (pintype "passive"))
      (node (ref "L2") (pin "2") (pinfunction "2_2") (pintype "passive"))
      (node (ref "R7") (pin "2") (pinfunction "2_2") (pintype "passive"))
      (node (ref "RN1") (pin "1") (pinfunction "1_1") (pintype "passive"))
      (node (ref "RN4") (pin "1") (pinfunction "1_1") (pintype "passive"))
      (node (ref "RN4") (pin "7") (pinfunction "1_7") (pintype "passive"))
    )
    (net (code "85") (name "unconnected-(IC3-SQW{slash}OUT-Pad7)") (class "Default")
      (node (ref "IC3") (pin "7") (pinfunction "SQW/OUT_7") (pintype "bidirectional"))
    )
    (net (code "86") (name "unconnected-(IC6-CLKOUT-Pad3)") (class "Default")
      (node (ref "IC6") (pin "3") (pinfunction "CLKOUT_3") (pintype "output"))
    )
    (net (code "87") (name "unconnected-(IC6-NC*-Pad5)") (class "Default")
      (node (ref "IC6") (pin "5") (pinfunction "NC*_5") (pintype "output"))
    )
    (net (code "88") (name "unconnected-(IC6-~{INT}-Pad4)") (class "Default")
      (node (ref "IC6") (pin "4") (pinfunction "~{INT}_4") (pintype "output"))
    )
    (net (code "89") (name "unconnected-(IC8-PadANT)") (class "Default")
      (node (ref "IC8") (pin "ANT") (pinfunction "ANT_ANT") (pintype "passive"))
    )
    (net (code "90") (name "unconnected-(IC8-PadFFS)") (class "Default")
      (node (ref "IC8") (pin "FFS") (pinfunction "FFS_FFS") (pintype "bidirectional"))
    )
    (net (code "91") (name "unconnected-(J2-O-Pad1)") (class "Default")
      (node (ref "J2") (pin "1") (pinfunction "O_1") (pintype "passive"))
    )
    (net (code "92") (name "unconnected-(LCD-DB0-Pad7)") (class "Default")
      (node (ref "LCD") (pin "7") (pinfunction "DB0_7") (pintype "bidirectional"))
    )
    (net (code "93") (name "unconnected-(LCD-DB1-Pad8)") (class "Default")
      (node (ref "LCD") (pin "8") (pinfunction "DB1_8") (pintype "bidirectional"))
    )
    (net (code "94") (name "unconnected-(LCD-DB2-Pad9)") (class "Default")
      (node (ref "LCD") (pin "9") (pinfunction "DB2_9") (pintype "bidirectional"))
    )
    (net (code "95") (name "unconnected-(LCD-DB3-Pad10)") (class "Default")
      (node (ref "LCD") (pin "10") (pinfunction "DB3_10") (pintype "bidirectional"))
    )
    (net (code "96") (name "unconnected-(RJ1-PadNC)") (class "Default")
      (node (ref "RJ1") (pin "NC") (pinfunction "NC_NC") (pintype "bidirectional"))
    )
    (net (code "97") (name "unconnected-(RJ1-PadP5)") (class "Default")
      (node (ref "RJ1") (pin "P5") (pinfunction "P5_P5") (pintype "bidirectional"))
    )
  )
)
